# 24_cup_wash_sucction.net
KiCad netlist of a schematic drawn in EAGLE
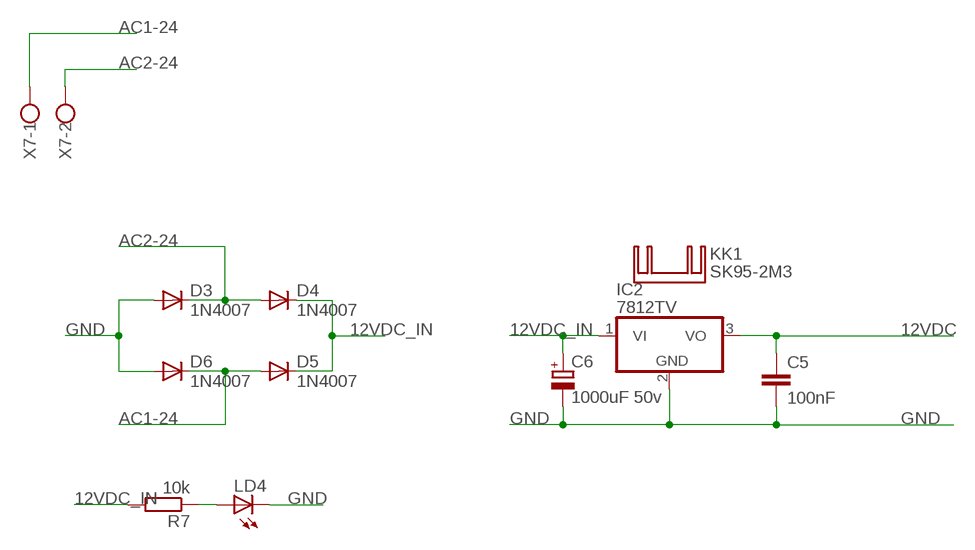
[diagram p0: schematic, sheet 1]
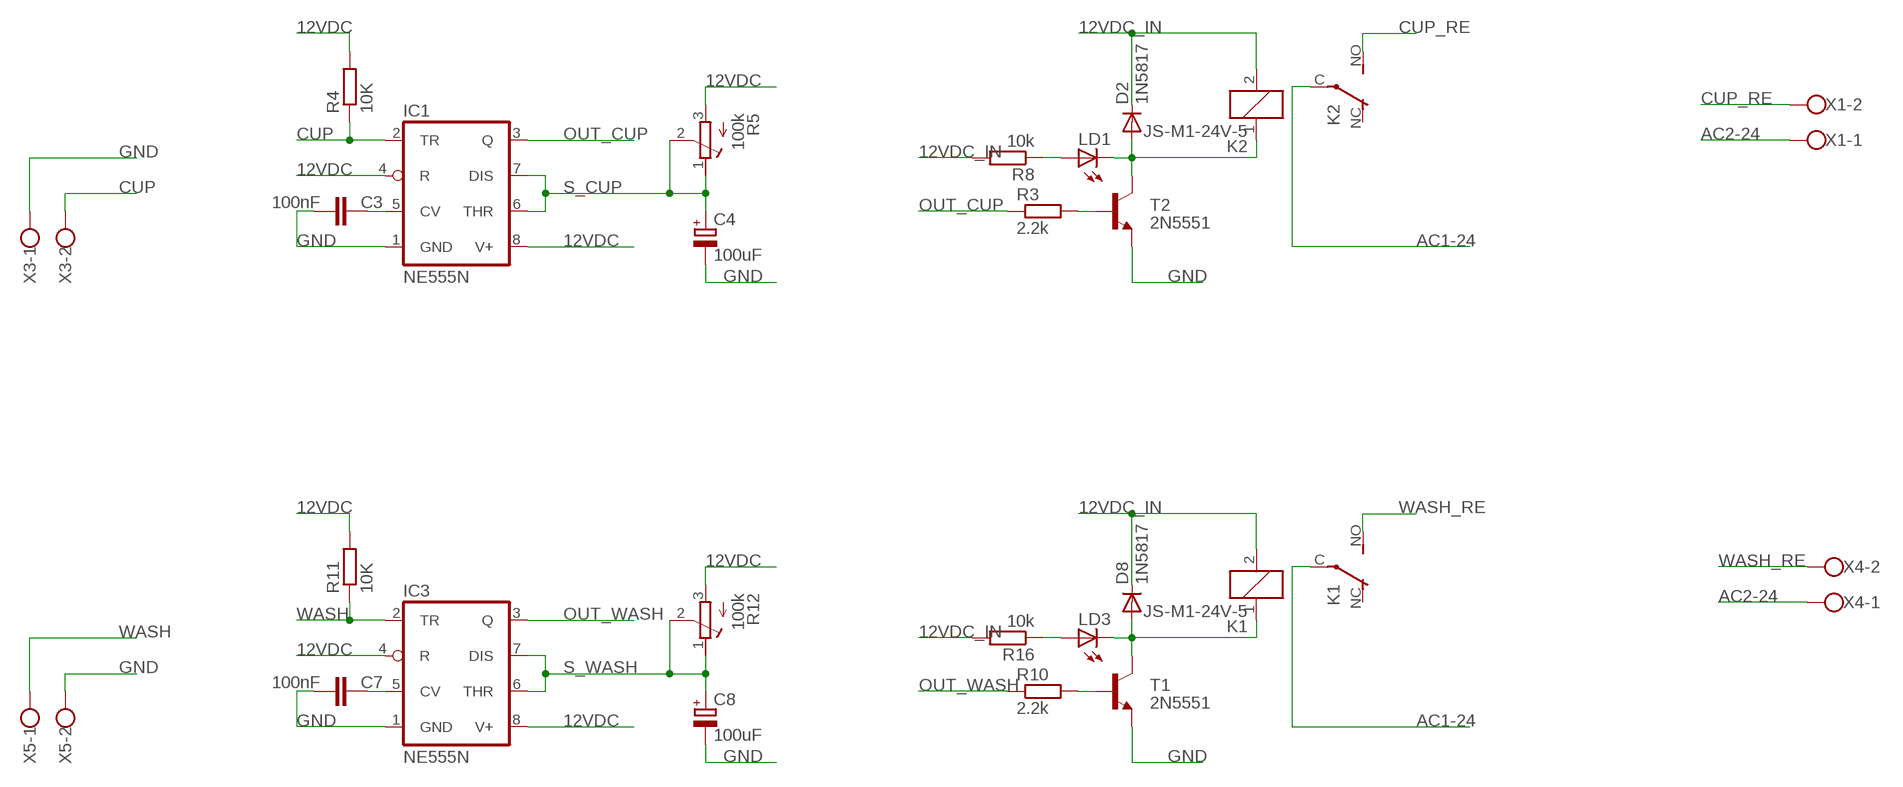
[diagram p1: schematic, sheet 2]
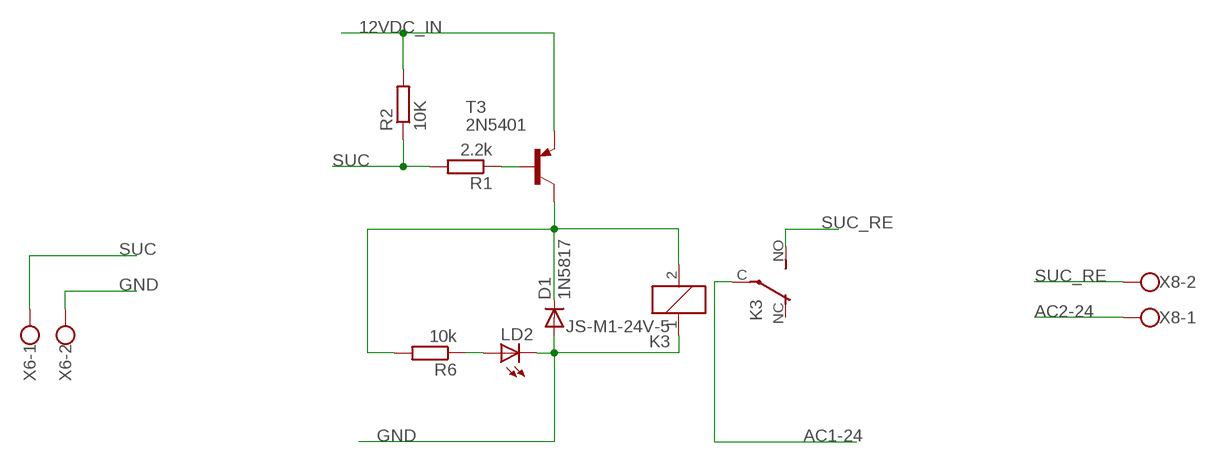
[diagram p2: schematic, sheet 3]

(export (version "E")
  (design (tool "Eeschema 10.0.6"))
  (components
    (comp (ref "D1")
      (value "1N5817")
      (footprint "eagle-import:DO41-10")
      (libsource (lib "eagle-import") (part "1N4004"))
    )
    (comp (ref "K3")
      (value "JS-M1-24V-5")
      (footprint "eagle-import:JS-M")
      (fields (field (name "MF") "FARNELL") (field (name "MPN") "JSM1-12V-5"))
      (libsource (lib "eagle-import") (part "JS-M1-12V-5"))
    )
    (comp (ref "LD2")
      (value "LED5MM")
      (footprint "eagle-import:LED5MM")
      (libsource (lib "eagle-import") (part "LED5MM"))
    )
    (comp (ref "R1")
      (value "2.2k")
      (footprint "eagle-import:0207_10")
      (libsource (lib "eagle-import") (part "R-EU_0207/10"))
    )
    (comp (ref "R2")
      (value "10K")
      (footprint "eagle-import:0207_10")
      (libsource (lib "eagle-import") (part "R-EU_0207/10"))
    )
    (comp (ref "R6")
      (value "10k")
      (footprint "eagle-import:0207_10")
      (libsource (lib "eagle-import") (part "R-EU_0207/10"))
    )
    (comp (ref "T3")
      (value "2N5401")
      (footprint "eagle-import:TO92-EBC")
      (libsource (lib "eagle-import") (part "-PNP-TO92-EBC2N5401"))
    )
    (comp (ref "X6")
      (value "W237-102")
      (footprint "eagle-import:W237-102")
      (libsource (lib "eagle-import") (part "W237-102"))
    )
    (comp (ref "X8")
      (value "W237-102")
      (footprint "eagle-import:W237-102")
      (libsource (lib "eagle-import") (part "W237-102"))
    )
    (comp (ref "C5")
      (value "100nF")
      (footprint "eagle-import:C050-025X075")
      (libsource (lib "eagle-import") (part "C-EU050-025X075"))
    )
    (comp (ref "C6")
      (value "1000uF 50v")
      (footprint "eagle-import:E5-13")
      (libsource (lib "eagle-import") (part "CPOL-EUE5-13"))
    )
    (comp (ref "D3")
      (value "1N4007")
      (footprint "eagle-import:DO41-10")
      (libsource (lib "eagle-import") (part "adafruit_420_1N4004"))
    )
    (comp (ref "D4")
      (value "1N4007")
      (footprint "eagle-import:DO41-10")
      (libsource (lib "eagle-import") (part "adafruit_420_1N4004"))
    )
    (comp (ref "D5")
      (value "1N4007")
      (footprint "eagle-import:DO41-10")
      (libsource (lib "eagle-import") (part "adafruit_420_1N4004"))
    )
    (comp (ref "D6")
      (value "1N4007")
      (footprint "eagle-import:DO41-10")
      (libsource (lib "eagle-import") (part "adafruit_420_1N4004"))
    )
    (comp (ref "IC2")
      (value "7812TV")
      (footprint "eagle-import:TO220V")
      (libsource (lib "eagle-import") (part "78TV12"))
    )
    (comp (ref "KK1")
      (value "SK95-2M3")
      (footprint "eagle-import:SK95-2M3")
      (libsource (lib "eagle-import") (part "SK95-2M3"))
    )
    (comp (ref "LD4")
      (value "LED5MM")
      (footprint "eagle-import:LED5MM")
      (libsource (lib "eagle-import") (part "LED5MM"))
    )
    (comp (ref "R7")
      (value "10k")
      (footprint "eagle-import:0207_10")
      (libsource (lib "eagle-import") (part "R-EU_0207/10"))
    )
    (comp (ref "X7")
      (value "W237-102")
      (footprint "eagle-import:W237-102")
      (libsource (lib "eagle-import") (part "W237-102"))
    )
    (comp (ref "C3")
      (value "100nF")
      (footprint "eagle-import:C050-025X075")
      (libsource (lib "eagle-import") (part "C-EU050-025X075"))
    )
    (comp (ref "C4")
      (value "100uF")
      (footprint "eagle-import:E3,5-8")
      (libsource (lib "eagle-import") (part "CPOL-EUE3.5-8"))
    )
    (comp (ref "C7")
      (value "100nF")
      (footprint "eagle-import:C050-025X075")
      (libsource (lib "eagle-import") (part "C-EU050-025X075"))
    )
    (comp (ref "C8")
      (value "100uF")
      (footprint "eagle-import:E3,5-8")
      (libsource (lib "eagle-import") (part "CPOL-EUE3.5-8"))
    )
    (comp (ref "D2")
      (value "1N5817")
      (footprint "eagle-import:DO41-10")
      (libsource (lib "eagle-import") (part "1N4004"))
    )
    (comp (ref "D8")
      (value "1N5817")
      (footprint "eagle-import:DO41-10")
      (libsource (lib "eagle-import") (part "1N4004"))
    )
    (comp (ref "IC1")
      (value "NE555N")
      (footprint "eagle-import:DIL08-ROUND")
      (libsource (lib "eagle-import") (part "555NNE"))
    )
    (comp (ref "IC3")
      (value "NE555N")
      (footprint "eagle-import:DIL08-ROUND")
      (libsource (lib "eagle-import") (part "555NNE"))
    )
    (comp (ref "K1")
      (value "JS-M1-24V-5")
      (footprint "eagle-import:JS-M")
      (fields (field (name "MF") "FARNELL") (field (name "MPN") "JSM1-12V-5"))
      (libsource (lib "eagle-import") (part "JS-M1-12V-5"))
    )
    (comp (ref "K2")
      (value "JS-M1-24V-5")
      (footprint "eagle-import:JS-M")
      (fields (field (name "MF") "FARNELL") (field (name "MPN") "JSM1-12V-5"))
      (libsource (lib "eagle-import") (part "JS-M1-12V-5"))
    )
    (comp (ref "LD1")
      (value "LED5MM")
      (footprint "eagle-import:LED5MM")
      (libsource (lib "eagle-import") (part "LED5MM"))
    )
    (comp (ref "LD3")
      (value "LED5MM")
      (footprint "eagle-import:LED5MM")
      (libsource (lib "eagle-import") (part "LED5MM"))
    )
    (comp (ref "R3")
      (value "2.2k")
      (footprint "eagle-import:0207_10")
      (libsource (lib "eagle-import") (part "R-EU_0207/10"))
    )
    (comp (ref "R4")
      (value "10K")
      (footprint "eagle-import:0207_10")
      (libsource (lib "eagle-import") (part "R-EU_0207/10"))
    )
    (comp (ref "R5")
      (value "100k")
      (footprint "eagle-import:RTRIMT93XA")
      (libsource (lib "eagle-import") (part "R-TRIMMT93XA"))
    )
    (comp (ref "R8")
      (value "10k")
      (footprint "eagle-import:0207_10")
      (libsource (lib "eagle-import") (part "R-EU_0207/10"))
    )
    (comp (ref "R10")
      (value "2.2k")
      (footprint "eagle-import:0207_10")
      (libsource (lib "eagle-import") (part "R-EU_0207/10"))
    )
    (comp (ref "R11")
      (value "10K")
      (footprint "eagle-import:0207_10")
      (libsource (lib "eagle-import") (part "R-EU_0207/10"))
    )
    (comp (ref "R12")
      (value "100k")
      (footprint "eagle-import:RTRIMT93XA")
      (libsource (lib "eagle-import") (part "R-TRIMMT93XA"))
    )
    (comp (ref "R16")
      (value "10k")
      (footprint "eagle-import:0207_10")
      (libsource (lib "eagle-import") (part "R-EU_0207/10"))
    )
    (comp (ref "T1")
      (value "2N5551")
      (footprint "eagle-import:TO92-EBC-OVAL")
      (libsource (lib "eagle-import") (part "2N2222"))
    )
    (comp (ref "T2")
      (value "2N5551")
      (footprint "eagle-import:TO92-EBC-OVAL")
      (libsource (lib "eagle-import") (part "2N2222"))
    )
    (comp (ref "X1")
      (value "W237-102")
      (footprint "eagle-import:W237-102")
      (libsource (lib "eagle-import") (part "W237-102"))
    )
    (comp (ref "X3")
      (value "W237-102")
      (footprint "eagle-import:W237-102")
      (libsource (lib "eagle-import") (part "W237-102"))
    )
    (comp (ref "X4")
      (value "W237-102")
      (footprint "eagle-import:W237-102")
      (libsource (lib "eagle-import") (part "W237-102"))
    )
    (comp (ref "X5")
      (value "W237-102")
      (footprint "eagle-import:W237-102")
      (libsource (lib "eagle-import") (part "W237-102"))
    )
  )
  (nets
    (net (code "1") (name "12VDC") (class "Default")
      (node (ref "C5") (pin "1") (pinfunction "1_1") (pintype "passive"))
      (node (ref "IC1") (pin "4") (pinfunction "R_4") (pintype "input"))
      (node (ref "IC1") (pin "8") (pinfunction "V+_8") (pintype "power_in"))
      (node (ref "IC2") (pin "3") (pinfunction "VO_3") (pintype "passive"))
      (node (ref "IC3") (pin "4") (pinfunction "R_4") (pintype "input"))
      (node (ref "IC3") (pin "8") (pinfunction "V+_8") (pintype "power_in"))
      (node (ref "R11") (pin "2") (pinfunction "2_2") (pintype "passive"))
      (node (ref "R12") (pin "3") (pinfunction "A_3") (pintype "passive"))
      (node (ref "R4") (pin "2") (pinfunction "2_2") (pintype "passive"))
      (node (ref "R5") (pin "3") (pinfunction "A_3") (pintype "passive"))
    )
    (net (code "2") (name "12VDC_IN") (class "Default")
      (node (ref "C6") (pin "+") (pinfunction "+_+") (pintype "passive"))
      (node (ref "D2") (pin "C") (pinfunction "C_C") (pintype "passive"))
      (node (ref "D4") (pin "C") (pinfunction "C_C") (pintype "passive"))
      (node (ref "D5") (pin "C") (pinfunction "C_C") (pintype "passive"))
      (node (ref "D8") (pin "C") (pinfunction "C_C") (pintype "passive"))
      (node (ref "IC2") (pin "1") (pinfunction "VI_1") (pintype "input"))
      (node (ref "K1") (pin "2") (pinfunction "2_2") (pintype "passive"))
      (node (ref "K2") (pin "2") (pinfunction "2_2") (pintype "passive"))
      (node (ref "R16") (pin "2") (pinfunction "2_2") (pintype "passive"))
      (node (ref "R2") (pin "2") (pinfunction "2_2") (pintype "passive"))
      (node (ref "R7") (pin "2") (pinfunction "2_2") (pintype "passive"))
      (node (ref "R8") (pin "2") (pinfunction "2_2") (pintype "passive"))
      (node (ref "T3") (pin "E") (pinfunction "E_E") (pintype "passive"))
    )
    (net (code "3") (name "AC1-24") (class "Default")
      (node (ref "D5") (pin "A") (pinfunction "A_A") (pintype "passive"))
      (node (ref "D6") (pin "C") (pinfunction "C_C") (pintype "passive"))
      (node (ref "K1") (pin "C") (pinfunction "P_C") (pintype "passive"))
      (node (ref "K2") (pin "C") (pinfunction "P_C") (pintype "passive"))
      (node (ref "K3") (pin "C") (pinfunction "P_C") (pintype "passive"))
      (node (ref "X7") (pin "1") (pinfunction "KL_1") (pintype "passive"))
    )
    (net (code "4") (name "AC2-24") (class "Default")
      (node (ref "D3") (pin "C") (pinfunction "C_C") (pintype "passive"))
      (node (ref "D4") (pin "A") (pinfunction "A_A") (pintype "passive"))
      (node (ref "X1") (pin "1") (pinfunction "KL_1") (pintype "passive"))
      (node (ref "X4") (pin "1") (pinfunction "KL_1") (pintype "passive"))
      (node (ref "X7") (pin "2") (pinfunction "KL_2") (pintype "passive"))
      (node (ref "X8") (pin "1") (pinfunction "KL_1") (pintype "passive"))
    )
    (net (code "5") (name "CUP") (class "Default")
      (node (ref "IC1") (pin "2") (pinfunction "TR_2") (pintype "input"))
      (node (ref "R4") (pin "1") (pinfunction "1_1") (pintype "passive"))
      (node (ref "X3") (pin "2") (pinfunction "KL_2") (pintype "passive"))
    )
    (net (code "6") (name "CUP_RE") (class "Default")
      (node (ref "K2") (pin "NO") (pinfunction "S_NO") (pintype "passive"))
      (node (ref "X1") (pin "2") (pinfunction "KL_2") (pintype "passive"))
    )
    (net (code "7") (name "GND") (class "Default")
      (node (ref "C3") (pin "2") (pinfunction "2_2") (pintype "passive"))
      (node (ref "C4") (pin "-") (pinfunction "-_-") (pintype "passive"))
      (node (ref "C5") (pin "2") (pinfunction "2_2") (pintype "passive"))
      (node (ref "C6") (pin "-") (pinfunction "-_-") (pintype "passive"))
      (node (ref "C7") (pin "2") (pinfunction "2_2") (pintype "passive"))
      (node (ref "C8") (pin "-") (pinfunction "-_-") (pintype "passive"))
      (node (ref "D1") (pin "A") (pinfunction "A_A") (pintype "passive"))
      (node (ref "D3") (pin "A") (pinfunction "A_A") (pintype "passive"))
      (node (ref "D6") (pin "A") (pinfunction "A_A") (pintype "passive"))
      (node (ref "IC1") (pin "1") (pinfunction "GND_1") (pintype "power_in"))
      (node (ref "IC2") (pin "2") (pinfunction "GND_2") (pintype "passive"))
      (node (ref "IC3") (pin "1") (pinfunction "GND_1") (pintype "power_in"))
      (node (ref "K3") (pin "1") (pinfunction "1_1") (pintype "passive"))
      (node (ref "LD2") (pin "K") (pinfunction "C_K") (pintype "passive"))
      (node (ref "LD4") (pin "K") (pinfunction "C_K") (pintype "passive"))
      (node (ref "T1") (pin "E") (pinfunction "E_E") (pintype "passive"))
      (node (ref "T2") (pin "E") (pinfunction "E_E") (pintype "passive"))
      (node (ref "X3") (pin "1") (pinfunction "KL_1") (pintype "passive"))
      (node (ref "X5") (pin "2") (pinfunction "KL_2") (pintype "passive"))
      (node (ref "X6") (pin "2") (pinfunction "KL_2") (pintype "passive"))
    )
    (net (code "8") (name "Net-(D1-PadC)") (class "Default")
      (node (ref "D1") (pin "C") (pinfunction "C_C") (pintype "passive"))
      (node (ref "K3") (pin "2") (pinfunction "2_2") (pintype "passive"))
      (node (ref "R6") (pin "2") (pinfunction "2_2") (pintype "passive"))
      (node (ref "T3") (pin "C") (pinfunction "C_C") (pintype "passive"))
    )
    (net (code "9") (name "Net-(IC1-CV)") (class "Default")
      (node (ref "C3") (pin "1") (pinfunction "1_1") (pintype "passive"))
      (node (ref "IC1") (pin "5") (pinfunction "CV_5") (pintype "input"))
    )
    (net (code "10") (name "Net-(IC3-CV)") (class "Default")
      (node (ref "C7") (pin "1") (pinfunction "1_1") (pintype "passive"))
      (node (ref "IC3") (pin "5") (pinfunction "CV_5") (pintype "input"))
    )
    (net (code "11") (name "Net-(LD1-C)") (class "Default")
      (node (ref "D2") (pin "A") (pinfunction "A_A") (pintype "passive"))
      (node (ref "K2") (pin "1") (pinfunction "1_1") (pintype "passive"))
      (node (ref "LD1") (pin "K") (pinfunction "C_K") (pintype "passive"))
      (node (ref "T2") (pin "C") (pinfunction "C_C") (pintype "passive"))
    )
    (net (code "12") (name "Net-(LD1-PadA)") (class "Default")
      (node (ref "LD1") (pin "A") (pinfunction "A_A") (pintype "passive"))
      (node (ref "R8") (pin "1") (pinfunction "1_1") (pintype "passive"))
    )
    (net (code "13") (name "Net-(LD2-PadA)") (class "Default")
      (node (ref "LD2") (pin "A") (pinfunction "A_A") (pintype "passive"))
      (node (ref "R6") (pin "1") (pinfunction "1_1") (pintype "passive"))
    )
    (net (code "14") (name "Net-(LD3-C)") (class "Default")
      (node (ref "D8") (pin "A") (pinfunction "A_A") (pintype "passive"))
      (node (ref "K1") (pin "1") (pinfunction "1_1") (pintype "passive"))
      (node (ref "LD3") (pin "K") (pinfunction "C_K") (pintype "passive"))
      (node (ref "T1") (pin "C") (pinfunction "C_C") (pintype "passive"))
    )
    (net (code "15") (name "Net-(LD3-PadA)") (class "Default")
      (node (ref "LD3") (pin "A") (pinfunction "A_A") (pintype "passive"))
      (node (ref "R16") (pin "1") (pinfunction "1_1") (pintype "passive"))
    )
    (net (code "16") (name "Net-(LD4-PadA)") (class "Default")
      (node (ref "LD4") (pin "A") (pinfunction "A_A") (pintype "passive"))
      (node (ref "R7") (pin "1") (pinfunction "1_1") (pintype "passive"))
    )
    (net (code "17") (name "Net-(R1-Pad1)") (class "Default")
      (node (ref "R1") (pin "1") (pinfunction "1_1") (pintype "passive"))
      (node (ref "T3") (pin "B") (pinfunction "B_B") (pintype "passive"))
    )
    (net (code "18") (name "Net-(R3-Pad2)") (class "Default")
      (node (ref "R3") (pin "2") (pinfunction "2_2") (pintype "passive"))
      (node (ref "T2") (pin "B") (pinfunction "B_B") (pintype "passive"))
    )
    (net (code "19") (name "Net-(R10-Pad2)") (class "Default")
      (node (ref "R10") (pin "2") (pinfunction "2_2") (pintype "passive"))
      (node (ref "T1") (pin "B") (pinfunction "B_B") (pintype "passive"))
    )
    (net (code "20") (name "OUT_CUP") (class "Default")
      (node (ref "IC1") (pin "3") (pinfunction "Q_3") (pintype "output"))
      (node (ref "R3") (pin "1") (pinfunction "1_1") (pintype "passive"))
    )
    (net (code "21") (name "OUT_WASH") (class "Default")
      (node (ref "IC3") (pin "3") (pinfunction "Q_3") (pintype "output"))
      (node (ref "R10") (pin "1") (pinfunction "1_1") (pintype "passive"))
    )
    (net (code "22") (name "SUC") (class "Default")
      (node (ref "R1") (pin "2") (pinfunction "2_2") (pintype "passive"))
      (node (ref "R2") (pin "1") (pinfunction "1_1") (pintype "passive"))
      (node (ref "X6") (pin "1") (pinfunction "KL_1") (pintype "passive"))
    )
    (net (code "23") (name "SUC_RE") (class "Default")
      (node (ref "K3") (pin "NO") (pinfunction "S_NO") (pintype "passive"))
      (node (ref "X8") (pin "2") (pinfunction "KL_2") (pintype "passive"))
    )
    (net (code "24") (name "S_CUP") (class "Default")
      (node (ref "C4") (pin "+") (pinfunction "+_+") (pintype "passive"))
      (node (ref "IC1") (pin "6") (pinfunction "THR_6") (pintype "input"))
      (node (ref "IC1") (pin "7") (pinfunction "DIS_7") (pintype "input"))
      (node (ref "R5") (pin "1") (pinfunction "E_1") (pintype "passive"))
      (node (ref "R5") (pin "2") (pinfunction "S_2") (pintype "passive"))
    )
    (net (code "25") (name "S_WASH") (class "Default")
      (node (ref "C8") (pin "+") (pinfunction "+_+") (pintype "passive"))
      (node (ref "IC3") (pin "6") (pinfunction "THR_6") (pintype "input"))
      (node (ref "IC3") (pin "7") (pinfunction "DIS_7") (pintype "input"))
      (node (ref "R12") (pin "1") (pinfunction "E_1") (pintype "passive"))
      (node (ref "R12") (pin "2") (pinfunction "S_2") (pintype "passive"))
    )
    (net (code "26") (name "WASH") (class "Default")
      (node (ref "IC3") (pin "2") (pinfunction "TR_2") (pintype "input"))
      (node (ref "R11") (pin "1") (pinfunction "1_1") (pintype "passive"))
      (node (ref "X5") (pin "1") (pinfunction "KL_1") (pintype "passive"))
    )
    (net (code "27") (name "WASH_RE") (class "Default")
      (node (ref "K1") (pin "NO") (pinfunction "S_NO") (pintype "passive"))
      (node (ref "X4") (pin "2") (pinfunction "KL_2") (pintype "passive"))
    )
    (net (code "28") (name "unconnected-(K1B-O-PadNC)") (class "Default")
      (node (ref "K1") (pin "NC") (pinfunction "O_NC") (pintype "passive"))
    )
    (net (code "29") (name "unconnected-(K2B-O-PadNC)") (class "Default")
      (node (ref "K2") (pin "NC") (pinfunction "O_NC") (pintype "passive"))
    )
    (net (code "30") (name "unconnected-(K3B-O-PadNC)") (class "Default")
      (node (ref "K3") (pin "NC") (pinfunction "O_NC") (pintype "passive"))
    )
  )
)
